# 08_RADAR_INTERFACE.net
KiCad netlist of a schematic drawn in Altium Designer
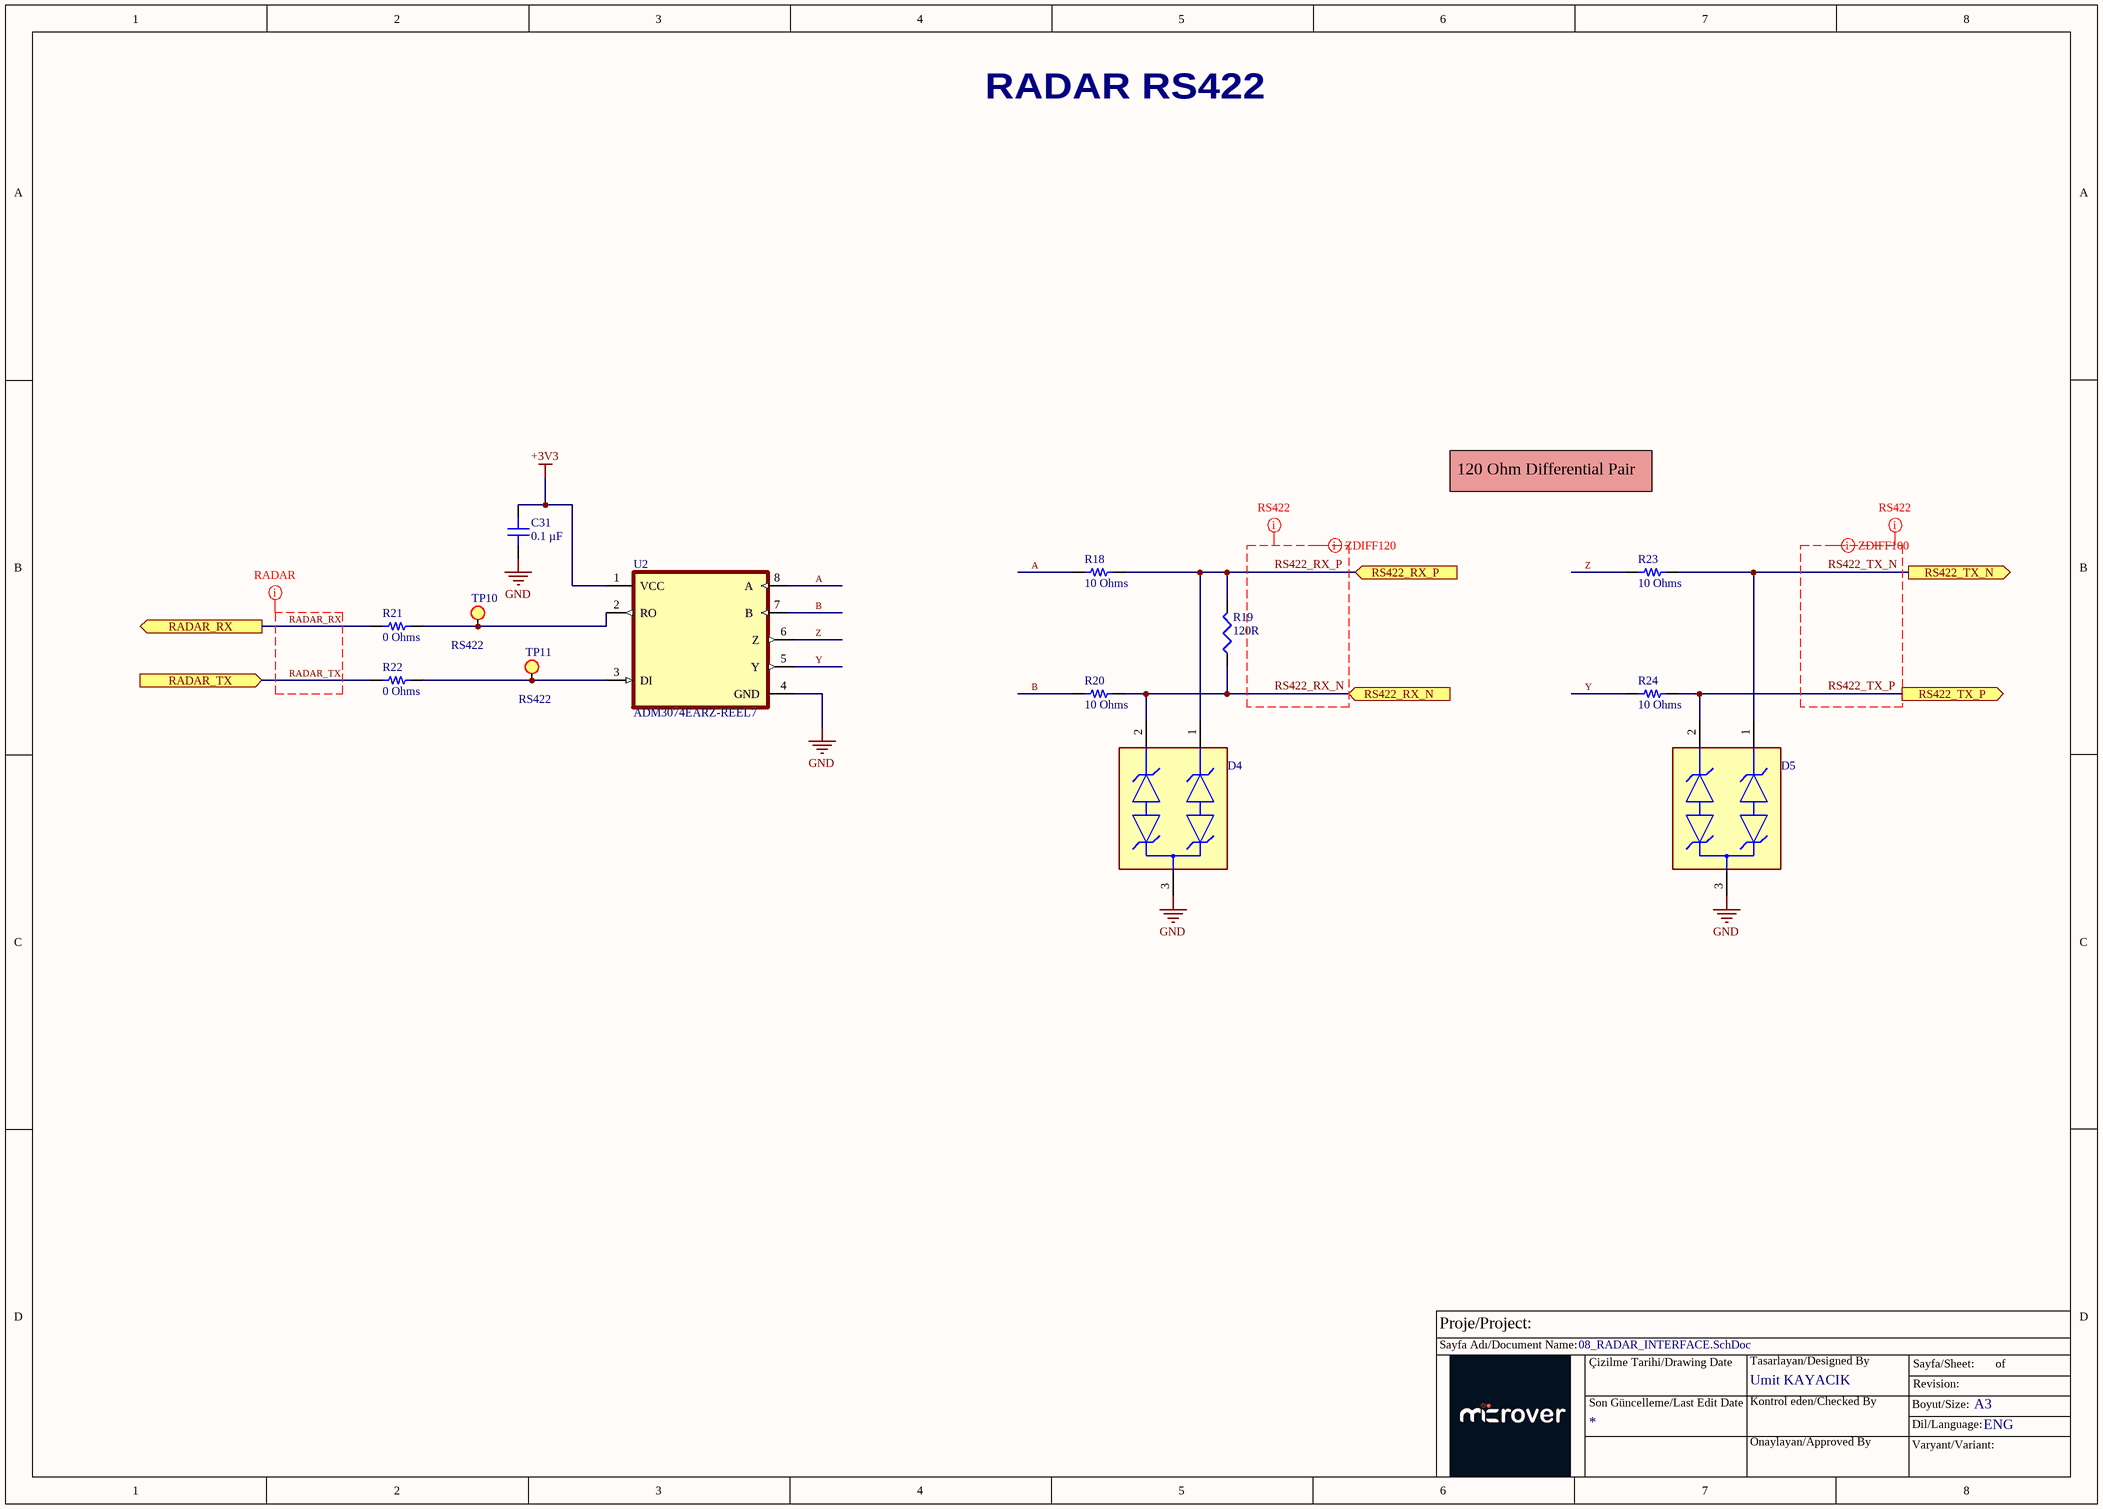
[diagram p0: 08_RADAR_INTERFACE.SchDoc]

(export (version "E")
  (design (tool "Eeschema 10.0.6"))
  (components
    (comp (ref "C31")
      (value "0.1 µF")
      (footprint "CAP 0603_1608")
      (description "CAP CER 0.1UF 50V X7R 0603")
      (fields
        (field (name "PART NUMBER") "VJ0603Y104KXAPW1BC")
        (field (name "MANUFACTURER") "Vishay Vitramon")
      )
      (libsource (lib "Celestial Altium Library - altium_library") (part "Capacitor"))
    )
    (comp (ref "D4")
      (value "SM712-02HTG")
      (footprint "Littelfuse_SM712_MFG")
      (libsource (lib "HW_HOLLAND_NCDM_MONITOR_R1") (part "SM712-02HTG"))
    )
    (comp (ref "D5")
      (value "SM712-02HTG")
      (footprint "Littelfuse_SM712_MFG")
      (libsource (lib "HW_HOLLAND_NCDM_MONITOR_R1") (part "SM712-02HTG"))
    )
    (comp (ref "R18")
      (value "10 Ohms")
      (footprint "RES 0603_1608")
      (description "RES SMD 10 OHM 1% 1/3W 0603")
      (fields
        (field (name "PART NUMBER") "ERJ-PA3F10R0V")
        (field (name "MANUFACTURER") "Panasonic Electronic Components")
      )
      (libsource (lib "Celestial Altium Library - altium_library") (part "Resistor"))
    )
    (comp (ref "R19")
      (value "120R")
      (footprint "RES1206")
      (description "120 Ohms ±1% 0.5W, 1/2W Chip Resistor 1206 (3216 Metric) Thick Film")
      (fields
        (field (name "MANUFACTURER PART NUMBER") "CRGH1206F120R")
        (field (name "Comment") "RES SMD 120 OHM 1% 1/2W 1206")
      )
      (libsource (lib "HW_HOLLAND_NCDM_MONITOR_R1") (part "RES1206_120R_%1"))
    )
    (comp (ref "R20")
      (value "10 Ohms")
      (footprint "RES 0603_1608")
      (description "RES SMD 10 OHM 1% 1/3W 0603")
      (fields
        (field (name "PART NUMBER") "ERJ-PA3F10R0V")
        (field (name "MANUFACTURER") "Panasonic Electronic Components")
      )
      (libsource (lib "Celestial Altium Library - altium_library") (part "Resistor"))
    )
    (comp (ref "R21")
      (value "0 Ohms")
      (footprint "RES 0402_1005")
      (description "RES 0 OHM JUMPER 1/8W 0402")
      (fields
        (field (name "PART NUMBER") "HCJ0402ZT0R00")
        (field (name "MANUFACTURER") "Stackpole Electronics Inc")
      )
      (libsource (lib "Celestial Altium Library - altium_library") (part "Resistor"))
    )
    (comp (ref "R22")
      (value "0 Ohms")
      (footprint "RES 0402_1005")
      (description "RES 0 OHM JUMPER 1/8W 0402")
      (fields
        (field (name "PART NUMBER") "HCJ0402ZT0R00")
        (field (name "MANUFACTURER") "Stackpole Electronics Inc")
      )
      (libsource (lib "Celestial Altium Library - altium_library") (part "Resistor"))
    )
    (comp (ref "R23")
      (value "10 Ohms")
      (footprint "RES 0603_1608")
      (description "RES SMD 10 OHM 1% 1/3W 0603")
      (fields
        (field (name "PART NUMBER") "ERJ-PA3F10R0V")
        (field (name "MANUFACTURER") "Panasonic Electronic Components")
      )
      (libsource (lib "Celestial Altium Library - altium_library") (part "Resistor"))
    )
    (comp (ref "R24")
      (value "10 Ohms")
      (footprint "RES 0603_1608")
      (description "RES SMD 10 OHM 1% 1/3W 0603")
      (fields
        (field (name "PART NUMBER") "ERJ-PA3F10R0V")
        (field (name "MANUFACTURER") "Panasonic Electronic Components")
      )
      (libsource (lib "Celestial Altium Library - altium_library") (part "Resistor"))
    )
    (comp (ref "TP10")
      (value "RS422")
      (footprint "TEST_POINT")
      (libsource (lib "HW_HOLLAND_NCDM_MONITOR_R1") (part "TP_1"))
    )
    (comp (ref "TP11")
      (value "RS422")
      (footprint "TEST_POINT")
      (libsource (lib "HW_HOLLAND_NCDM_MONITOR_R1") (part "TP_1"))
    )
    (comp (ref "U2")
      (value "ADM3074EARZ-REEL7")
      (footprint "SOIC127P600X175-8N")
      (description "Single Transmitter/Receiver RS-422/RS-485 8-Pin SOIC N T/R")
      (fields (field (name "MANUFACTURER") "Analog Devices"))
      (libsource (lib "HW_HOLLAND_NCDM_MONITOR_R1") (part "ADM3074EARZ-REEL7"))
    )
  )
  (nets
    (net (code "1") (name "+3V3") (class "Default")
      (node (ref "C31") (pin "2") (pinfunction "2_2") (pintype "passive"))
      (node (ref "U2") (pin "1") (pinfunction "VCC_1") (pintype "power_in"))
    )
    (net (code "2") (name "/A") (class "Default")
      (node (ref "R18") (pin "1") (pinfunction "1_1") (pintype "passive"))
      (node (ref "U2") (pin "8") (pinfunction "A_8") (pintype "input"))
    )
    (net (code "3") (name "/B") (class "Default")
      (node (ref "R20") (pin "1") (pinfunction "1_1") (pintype "passive"))
      (node (ref "U2") (pin "7") (pinfunction "B_7") (pintype "input"))
    )
    (net (code "4") (name "/RADAR_RX") (class "Default")
      (node (ref "R21") (pin "2") (pinfunction "2_2") (pintype "passive"))
    )
    (net (code "5") (name "/RADAR_TX") (class "Default")
      (node (ref "R22") (pin "2") (pinfunction "2_2") (pintype "passive"))
    )
    (net (code "6") (name "/RS422_RX_N") (class "Default")
      (node (ref "D4") (pin "2") (pinfunction "2_2") (pintype "passive"))
      (node (ref "R19") (pin "1") (pinfunction "1_1") (pintype "passive"))
      (node (ref "R20") (pin "2") (pinfunction "2_2") (pintype "passive"))
    )
    (net (code "7") (name "/RS422_RX_P") (class "Default")
      (node (ref "D4") (pin "1") (pinfunction "1_1") (pintype "passive"))
      (node (ref "R18") (pin "2") (pinfunction "2_2") (pintype "passive"))
      (node (ref "R19") (pin "2") (pinfunction "2_2") (pintype "passive"))
    )
    (net (code "8") (name "/RS422_TX_N") (class "Default")
      (node (ref "D5") (pin "1") (pinfunction "1_1") (pintype "passive"))
      (node (ref "R23") (pin "2") (pinfunction "2_2") (pintype "passive"))
    )
    (net (code "9") (name "/RS422_TX_P") (class "Default")
      (node (ref "D5") (pin "2") (pinfunction "2_2") (pintype "passive"))
      (node (ref "R24") (pin "2") (pinfunction "2_2") (pintype "passive"))
    )
    (net (code "10") (name "/Y") (class "Default")
      (node (ref "R24") (pin "1") (pinfunction "1_1") (pintype "passive"))
      (node (ref "U2") (pin "5") (pinfunction "Y_5") (pintype "output"))
    )
    (net (code "11") (name "/Z") (class "Default")
      (node (ref "R23") (pin "1") (pinfunction "1_1") (pintype "passive"))
      (node (ref "U2") (pin "6") (pinfunction "Z_6") (pintype "output"))
    )
    (net (code "12") (name "GND") (class "Default")
      (node (ref "C31") (pin "1") (pinfunction "1_1") (pintype "passive"))
      (node (ref "D4") (pin "3") (pinfunction "3_3") (pintype "passive"))
      (node (ref "D5") (pin "3") (pinfunction "3_3") (pintype "passive"))
      (node (ref "U2") (pin "4") (pinfunction "GND_4") (pintype "passive"))
    )
    (net (code "13") (name "Net-(TP10-TP)") (class "Default")
      (node (ref "R21") (pin "1") (pinfunction "1_1") (pintype "passive"))
      (node (ref "TP10") (pin "1") (pinfunction "TP_1") (pintype "passive"))
      (node (ref "U2") (pin "2") (pinfunction "RO_2") (pintype "output"))
    )
    (net (code "14") (name "Net-(TP11-TP)") (class "Default")
      (node (ref "R22") (pin "1") (pinfunction "1_1") (pintype "passive"))
      (node (ref "TP11") (pin "1") (pinfunction "TP_1") (pintype "passive"))
      (node (ref "U2") (pin "3") (pinfunction "DI_3") (pintype "input"))
    )
  )
)
